# boardBase3.net
KiCad netlist of a schematic drawn in EAGLE
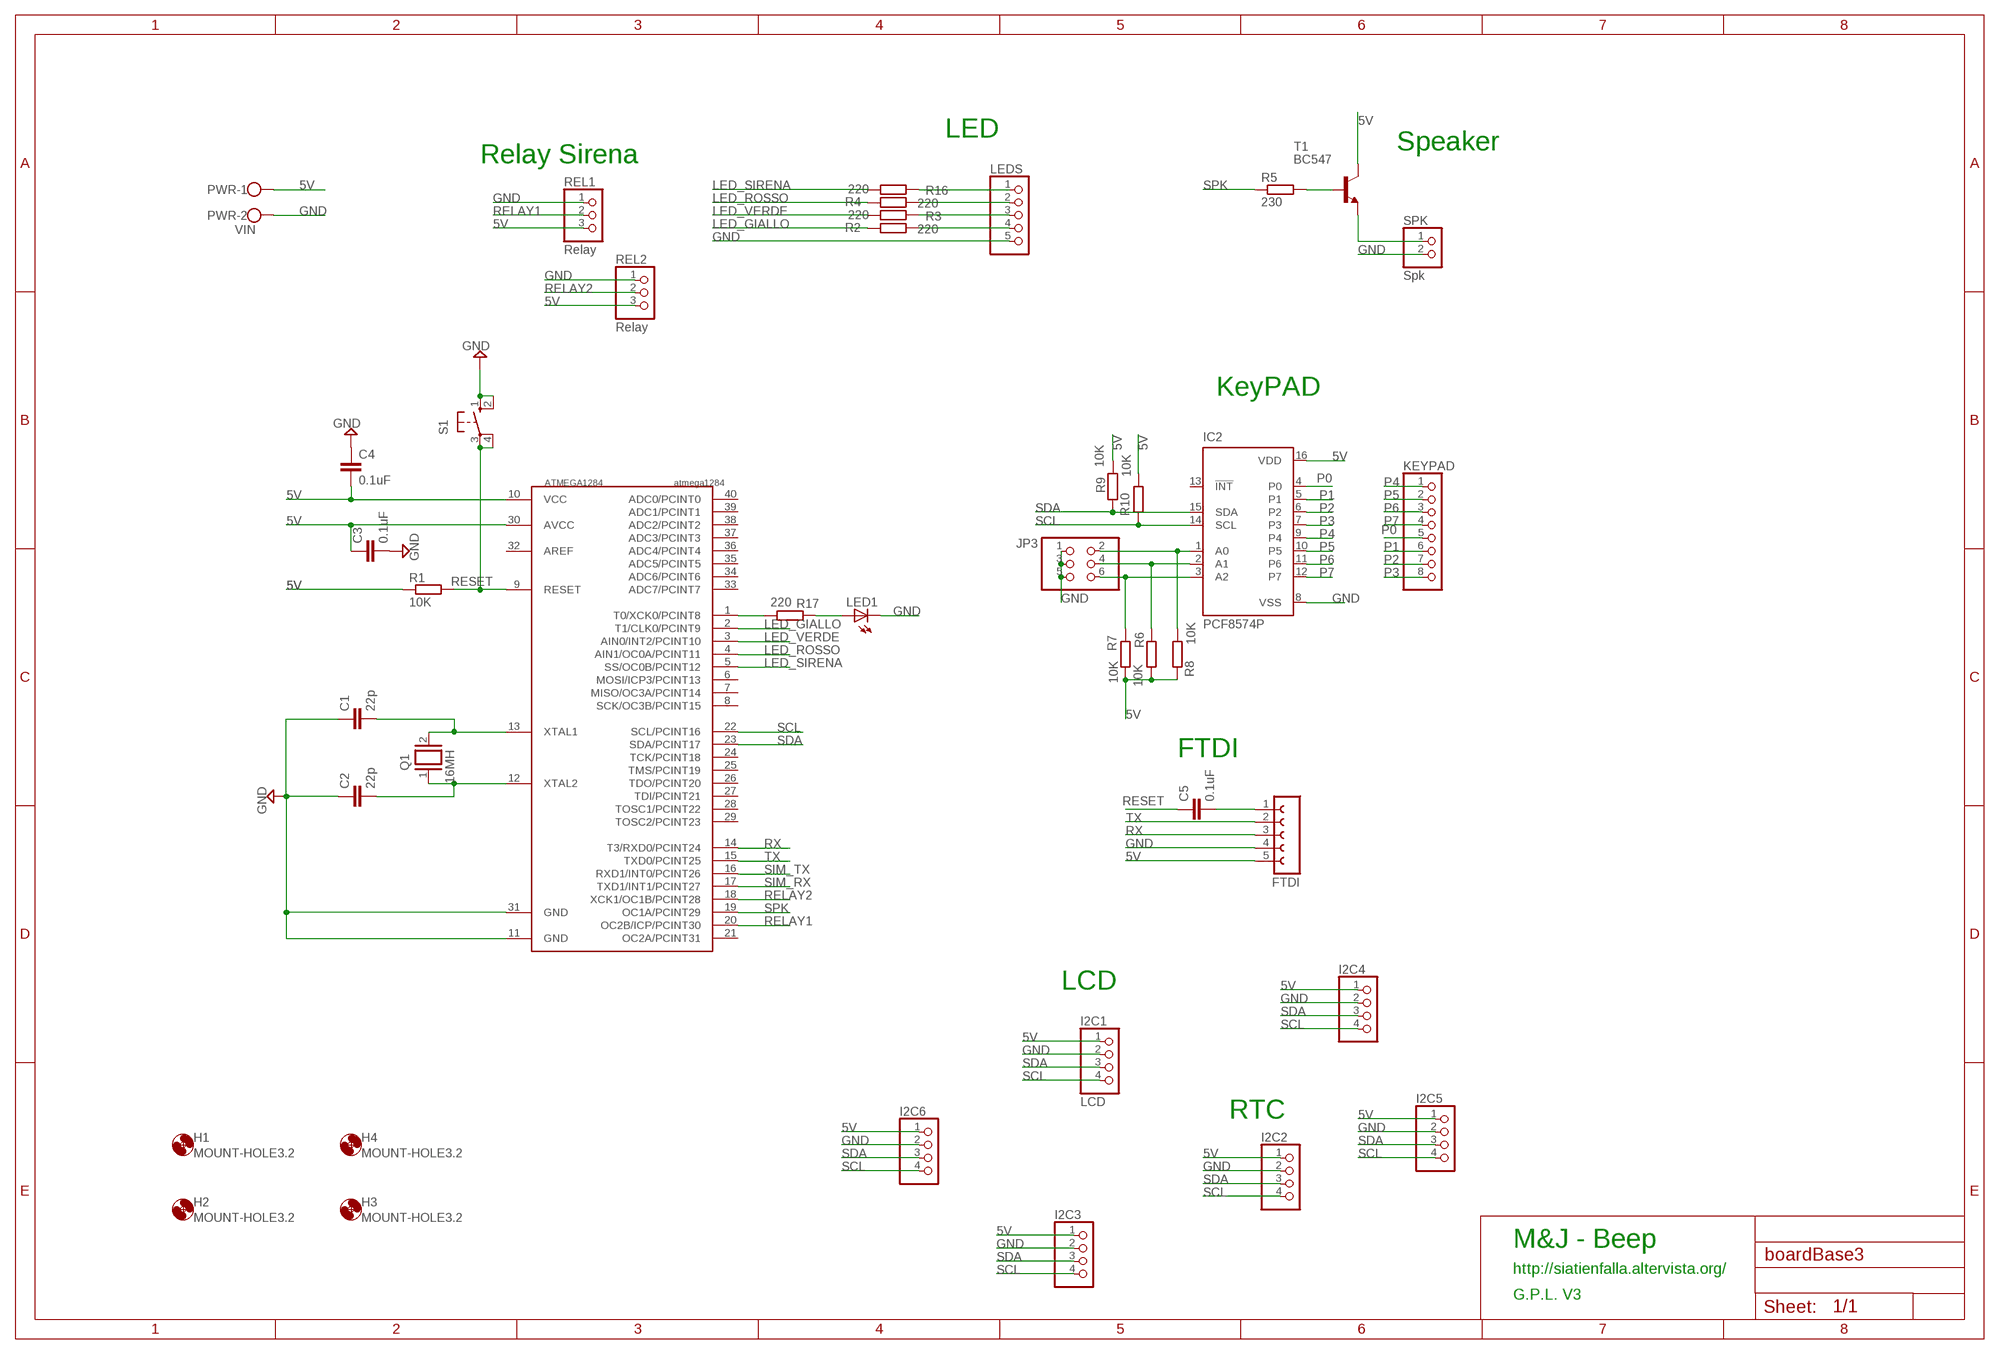
[diagram p0: schematic, sheet 1]

(export (version "E")
  (design (tool "Eeschema 10.0.6"))
  (components
    (comp (ref "ATMEGA1284")
      (value "atmega1284")
      (footprint "eagle-import:DIL40")
      (libsource (lib "eagle-import") (part "MEGA1284P"))
    )
    (comp (ref "C1")
      (value "22p")
      (footprint "eagle-import:C025-024X044")
      (libsource (lib "eagle-import") (part "C-EU025-024X044"))
    )
    (comp (ref "C2")
      (value "22p")
      (footprint "eagle-import:C025-024X044")
      (libsource (lib "eagle-import") (part "C-EU025-024X044"))
    )
    (comp (ref "C3")
      (value "0.1uF")
      (footprint "eagle-import:C025-025X050")
      (libsource (lib "eagle-import") (part "C-EU025-025X050"))
    )
    (comp (ref "C4")
      (value "0.1uF")
      (footprint "eagle-import:C025-025X050")
      (libsource (lib "eagle-import") (part "C-EU025-025X050"))
    )
    (comp (ref "C5")
      (value "0.1uF")
      (footprint "eagle-import:C025-025X050")
      (libsource (lib "eagle-import") (part "C-EU025-025X050"))
    )
    (comp (ref "FTDI")
      (value "FE05-1")
      (footprint "eagle-import:FE05-1")
      (libsource (lib "eagle-import") (part "FE05-1"))
    )
    (comp (ref "H1")
      (value "MOUNT-HOLE3.2")
      (footprint "eagle-import:3,2")
      (libsource (lib "eagle-import") (part "MOUNT-HOLE3.2"))
    )
    (comp (ref "H2")
      (value "MOUNT-HOLE3.2")
      (footprint "eagle-import:3,2")
      (libsource (lib "eagle-import") (part "MOUNT-HOLE3.2"))
    )
    (comp (ref "H3")
      (value "MOUNT-HOLE3.2")
      (footprint "eagle-import:3,2")
      (libsource (lib "eagle-import") (part "MOUNT-HOLE3.2"))
    )
    (comp (ref "H4")
      (value "MOUNT-HOLE3.2")
      (footprint "eagle-import:3,2")
      (libsource (lib "eagle-import") (part "MOUNT-HOLE3.2"))
    )
    (comp (ref "I2C1")
      (value "LCD")
      (footprint "eagle-import:1X04")
      (libsource (lib "eagle-import") (part "PINHD-1X4"))
    )
    (comp (ref "I2C2")
      (value "PINHD-1X4")
      (footprint "eagle-import:1X04")
      (libsource (lib "eagle-import") (part "PINHD-1X4"))
    )
    (comp (ref "I2C3")
      (value "PINHD-1X4")
      (footprint "eagle-import:1X04")
      (libsource (lib "eagle-import") (part "PINHD-1X4"))
    )
    (comp (ref "I2C4")
      (value "PINHD-1X4")
      (footprint "eagle-import:1X04")
      (libsource (lib "eagle-import") (part "PINHD-1X4"))
    )
    (comp (ref "I2C5")
      (value "PINHD-1X4")
      (footprint "eagle-import:1X04")
      (libsource (lib "eagle-import") (part "PINHD-1X4"))
    )
    (comp (ref "I2C6")
      (value "PINHD-1X4")
      (footprint "eagle-import:1X04")
      (libsource (lib "eagle-import") (part "PINHD-1X4"))
    )
    (comp (ref "IC2")
      (value "PCF8574P")
      (footprint "eagle-import:DIL16")
      (fields (field (name "MPN") "PCF8574PN"))
      (libsource (lib "eagle-import") (part "PCF8574P"))
    )
    (comp (ref "JP3")
      (value "PINHD-2X3")
      (footprint "eagle-import:2X03")
      (libsource (lib "eagle-import") (part "PINHD-2X3"))
    )
    (comp (ref "KEYPAD")
      (value "PINHD-1X8")
      (footprint "eagle-import:1X08")
      (libsource (lib "eagle-import") (part "PINHD-1X8"))
    )
    (comp (ref "LED1")
      (value "LED3MM")
      (footprint "eagle-import:LED3MM")
      (libsource (lib "eagle-import") (part "LED3MM"))
    )
    (comp (ref "LEDS")
      (value "PINHD-1X5")
      (footprint "eagle-import:1X05")
      (libsource (lib "eagle-import") (part "PINHD-1X5"))
    )
    (comp (ref "PWR")
      (value "VIN")
      (footprint "eagle-import:W237-102")
      (fields (field (name "MPN") "237-102"))
      (libsource (lib "eagle-import") (part "W237-102"))
    )
    (comp (ref "Q1")
      (value "16MH")
      (footprint "eagle-import:QS")
      (libsource (lib "eagle-import") (part "XTAL/S"))
    )
    (comp (ref "R1")
      (value "10K")
      (footprint "eagle-import:0207_10")
      (libsource (lib "eagle-import") (part "R-EU_0207/10"))
    )
    (comp (ref "R2")
      (value "220")
      (footprint "eagle-import:0207_2V")
      (libsource (lib "eagle-import") (part "R-EU_0207/2V"))
    )
    (comp (ref "R3")
      (value "220")
      (footprint "eagle-import:0207_2V")
      (libsource (lib "eagle-import") (part "R-EU_0207/2V"))
    )
    (comp (ref "R4")
      (value "220")
      (footprint "eagle-import:0207_2V")
      (libsource (lib "eagle-import") (part "R-EU_0207/2V"))
    )
    (comp (ref "R5")
      (value "230")
      (footprint "eagle-import:0207_2V")
      (libsource (lib "eagle-import") (part "R-EU_0207/2V"))
    )
    (comp (ref "R6")
      (value "10K")
      (footprint "eagle-import:0207_2V")
      (libsource (lib "eagle-import") (part "R-EU_0207/2V"))
    )
    (comp (ref "R7")
      (value "10K")
      (footprint "eagle-import:0207_2V")
      (libsource (lib "eagle-import") (part "R-EU_0207/2V"))
    )
    (comp (ref "R8")
      (value "10K")
      (footprint "eagle-import:0207_2V")
      (libsource (lib "eagle-import") (part "R-EU_0207/2V"))
    )
    (comp (ref "R9")
      (value "10K")
      (footprint "eagle-import:0207_2V")
      (libsource (lib "eagle-import") (part "R-EU_0207/2V"))
    )
    (comp (ref "R10")
      (value "10K")
      (footprint "eagle-import:0207_2V")
      (libsource (lib "eagle-import") (part "R-EU_0207/2V"))
    )
    (comp (ref "R16")
      (value "220")
      (footprint "eagle-import:0207_2V")
      (libsource (lib "eagle-import") (part "R-EU_0207/2V"))
    )
    (comp (ref "R17")
      (value "220")
      (footprint "eagle-import:0207_2V")
      (libsource (lib "eagle-import") (part "R-EU_0207/2V"))
    )
    (comp (ref "REL1")
      (value "Relay")
      (footprint "eagle-import:1X03")
      (libsource (lib "eagle-import") (part "PINHD-1X3"))
    )
    (comp (ref "REL2")
      (value "Relay")
      (footprint "eagle-import:1X03")
      (libsource (lib "eagle-import") (part "PINHD-1X3"))
    )
    (comp (ref "S1")
      (value "10-XX")
      (footprint "eagle-import:B3F-10XX")
      (fields (field (name "MPN") "B3F-1000"))
      (libsource (lib "eagle-import") (part "10-XX"))
    )
    (comp (ref "SPK")
      (value "Spk")
      (footprint "eagle-import:1X02")
      (libsource (lib "eagle-import") (part "PINHD-1X2"))
    )
    (comp (ref "T1")
      (value "BC547")
      (footprint "eagle-import:TO92")
      (libsource (lib "eagle-import") (part "BC547"))
    )
  )
  (nets
    (net (code "1") (name "/5V") (class "Default")
      (node (ref "ATMEGA1284") (pin "10") (pinfunction "VCC_10") (pintype "bidirectional"))
      (node (ref "ATMEGA1284") (pin "30") (pinfunction "AVCC_30") (pintype "bidirectional"))
      (node (ref "C3") (pin "1") (pinfunction "1_1") (pintype "passive"))
      (node (ref "C4") (pin "2") (pinfunction "2_2") (pintype "passive"))
      (node (ref "FTDI") (pin "5") (pinfunction "5_5") (pintype "passive"))
      (node (ref "I2C1") (pin "1") (pinfunction "1_1") (pintype "passive"))
      (node (ref "I2C2") (pin "1") (pinfunction "1_1") (pintype "passive"))
      (node (ref "I2C3") (pin "1") (pinfunction "1_1") (pintype "passive"))
      (node (ref "I2C4") (pin "1") (pinfunction "1_1") (pintype "passive"))
      (node (ref "I2C5") (pin "1") (pinfunction "1_1") (pintype "passive"))
      (node (ref "I2C6") (pin "1") (pinfunction "1_1") (pintype "passive"))
      (node (ref "IC2") (pin "16") (pinfunction "VDD_16") (pintype "power_in"))
      (node (ref "PWR") (pin "1") (pinfunction "KL_1") (pintype "passive"))
      (node (ref "R1") (pin "1") (pinfunction "1_1") (pintype "passive"))
      (node (ref "R10") (pin "1") (pinfunction "1_1") (pintype "passive"))
      (node (ref "R6") (pin "1") (pinfunction "1_1") (pintype "passive"))
      (node (ref "R7") (pin "2") (pinfunction "2_2") (pintype "passive"))
      (node (ref "R8") (pin "2") (pinfunction "2_2") (pintype "passive"))
      (node (ref "R9") (pin "2") (pinfunction "2_2") (pintype "passive"))
      (node (ref "REL1") (pin "3") (pinfunction "3_3") (pintype "passive"))
      (node (ref "REL2") (pin "3") (pinfunction "3_3") (pintype "passive"))
      (node (ref "T1") (pin "3") (pinfunction "C_3") (pintype "passive"))
    )
    (net (code "2") (name "/LED_GIALLO") (class "Default")
      (node (ref "ATMEGA1284") (pin "2") (pinfunction "T1/CLK0/PCINT9_2") (pintype "bidirectional"))
      (node (ref "R2") (pin "2") (pinfunction "2_2") (pintype "passive"))
    )
    (net (code "3") (name "/LED_ROSSO") (class "Default")
      (node (ref "ATMEGA1284") (pin "4") (pinfunction "AIN1/OC0A/PCINT11_4") (pintype "bidirectional"))
      (node (ref "R4") (pin "2") (pinfunction "2_2") (pintype "passive"))
    )
    (net (code "4") (name "/LED_SIRENA") (class "Default")
      (node (ref "ATMEGA1284") (pin "5") (pinfunction "SS/OC0B/PCINT12_5") (pintype "bidirectional"))
      (node (ref "R16") (pin "1") (pinfunction "1_1") (pintype "passive"))
    )
    (net (code "5") (name "/LED_VERDE") (class "Default")
      (node (ref "ATMEGA1284") (pin "3") (pinfunction "AIN0/INT2/PCINT10_3") (pintype "bidirectional"))
      (node (ref "R3") (pin "1") (pinfunction "1_1") (pintype "passive"))
    )
    (net (code "6") (name "/P0") (class "Default")
      (node (ref "IC2") (pin "4") (pinfunction "P0_4") (pintype "bidirectional"))
      (node (ref "KEYPAD") (pin "5") (pinfunction "5_5") (pintype "passive"))
    )
    (net (code "7") (name "/P1") (class "Default")
      (node (ref "IC2") (pin "5") (pinfunction "P1_5") (pintype "bidirectional"))
      (node (ref "KEYPAD") (pin "6") (pinfunction "6_6") (pintype "passive"))
    )
    (net (code "8") (name "/P2") (class "Default")
      (node (ref "IC2") (pin "6") (pinfunction "P2_6") (pintype "bidirectional"))
      (node (ref "KEYPAD") (pin "7") (pinfunction "7_7") (pintype "passive"))
    )
    (net (code "9") (name "/P3") (class "Default")
      (node (ref "IC2") (pin "7") (pinfunction "P3_7") (pintype "bidirectional"))
      (node (ref "KEYPAD") (pin "8") (pinfunction "8_8") (pintype "passive"))
    )
    (net (code "10") (name "/P4") (class "Default")
      (node (ref "IC2") (pin "9") (pinfunction "P4_9") (pintype "bidirectional"))
      (node (ref "KEYPAD") (pin "1") (pinfunction "1_1") (pintype "passive"))
    )
    (net (code "11") (name "/P5") (class "Default")
      (node (ref "IC2") (pin "10") (pinfunction "P5_10") (pintype "bidirectional"))
      (node (ref "KEYPAD") (pin "2") (pinfunction "2_2") (pintype "passive"))
    )
    (net (code "12") (name "/P6") (class "Default")
      (node (ref "IC2") (pin "11") (pinfunction "P6_11") (pintype "bidirectional"))
      (node (ref "KEYPAD") (pin "3") (pinfunction "3_3") (pintype "passive"))
    )
    (net (code "13") (name "/P7") (class "Default")
      (node (ref "IC2") (pin "12") (pinfunction "P7_12") (pintype "bidirectional"))
      (node (ref "KEYPAD") (pin "4") (pinfunction "4_4") (pintype "passive"))
    )
    (net (code "14") (name "/RELAY1") (class "Default")
      (node (ref "ATMEGA1284") (pin "20") (pinfunction "OC2B/ICP/PCINT30_20") (pintype "bidirectional"))
      (node (ref "REL1") (pin "2") (pinfunction "2_2") (pintype "passive"))
    )
    (net (code "15") (name "/RELAY2") (class "Default")
      (node (ref "ATMEGA1284") (pin "18") (pinfunction "XCK1/OC1B/PCINT28_18") (pintype "bidirectional"))
      (node (ref "REL2") (pin "2") (pinfunction "2_2") (pintype "passive"))
    )
    (net (code "16") (name "/RESET") (class "Default")
      (node (ref "ATMEGA1284") (pin "9") (pinfunction "RESET_9") (pintype "bidirectional"))
      (node (ref "C5") (pin "1") (pinfunction "1_1") (pintype "passive"))
      (node (ref "R1") (pin "2") (pinfunction "2_2") (pintype "passive"))
      (node (ref "S1") (pin "3") (pinfunction "P_3") (pintype "passive"))
      (node (ref "S1") (pin "4") (pinfunction "P1_4") (pintype "passive"))
    )
    (net (code "17") (name "/RX") (class "Default")
      (node (ref "ATMEGA1284") (pin "14") (pinfunction "T3/RXD0/PCINT24_14") (pintype "bidirectional"))
      (node (ref "FTDI") (pin "3") (pinfunction "3_3") (pintype "passive"))
    )
    (net (code "18") (name "/SCL") (class "Default")
      (node (ref "ATMEGA1284") (pin "22") (pinfunction "SCL/PCINT16_22") (pintype "bidirectional"))
      (node (ref "I2C1") (pin "4") (pinfunction "4_4") (pintype "passive"))
      (node (ref "I2C2") (pin "4") (pinfunction "4_4") (pintype "passive"))
      (node (ref "I2C3") (pin "4") (pinfunction "4_4") (pintype "passive"))
      (node (ref "I2C4") (pin "4") (pinfunction "4_4") (pintype "passive"))
      (node (ref "I2C5") (pin "4") (pinfunction "4_4") (pintype "passive"))
      (node (ref "I2C6") (pin "4") (pinfunction "4_4") (pintype "passive"))
      (node (ref "IC2") (pin "14") (pinfunction "SCL_14") (pintype "input"))
      (node (ref "R10") (pin "2") (pinfunction "2_2") (pintype "passive"))
    )
    (net (code "19") (name "/SDA") (class "Default")
      (node (ref "ATMEGA1284") (pin "23") (pinfunction "SDA/PCINT17_23") (pintype "bidirectional"))
      (node (ref "I2C1") (pin "3") (pinfunction "3_3") (pintype "passive"))
      (node (ref "I2C2") (pin "3") (pinfunction "3_3") (pintype "passive"))
      (node (ref "I2C3") (pin "3") (pinfunction "3_3") (pintype "passive"))
      (node (ref "I2C4") (pin "3") (pinfunction "3_3") (pintype "passive"))
      (node (ref "I2C5") (pin "3") (pinfunction "3_3") (pintype "passive"))
      (node (ref "I2C6") (pin "3") (pinfunction "3_3") (pintype "passive"))
      (node (ref "IC2") (pin "15") (pinfunction "SDA_15") (pintype "bidirectional"))
      (node (ref "R9") (pin "1") (pinfunction "1_1") (pintype "passive"))
    )
    (net (code "20") (name "/SIM_RX") (class "Default")
      (node (ref "ATMEGA1284") (pin "17") (pinfunction "TXD1/INT1/PCINT27_17") (pintype "bidirectional"))
    )
    (net (code "21") (name "/SIM_TX") (class "Default")
      (node (ref "ATMEGA1284") (pin "16") (pinfunction "RXD1/INT0/PCINT26_16") (pintype "bidirectional"))
    )
    (net (code "22") (name "/SPK") (class "Default")
      (node (ref "ATMEGA1284") (pin "19") (pinfunction "OC1A/PCINT29_19") (pintype "bidirectional"))
      (node (ref "R5") (pin "1") (pinfunction "1_1") (pintype "passive"))
    )
    (net (code "23") (name "/TX") (class "Default")
      (node (ref "ATMEGA1284") (pin "15") (pinfunction "TXD0/PCINT25_15") (pintype "bidirectional"))
      (node (ref "FTDI") (pin "2") (pinfunction "2_2") (pintype "passive"))
    )
    (net (code "24") (name "GND") (class "Default")
      (node (ref "ATMEGA1284") (pin "11") (pinfunction "GND_11") (pintype "bidirectional"))
      (node (ref "ATMEGA1284") (pin "31") (pinfunction "GND_31") (pintype "bidirectional"))
      (node (ref "C1") (pin "1") (pinfunction "1_1") (pintype "passive"))
      (node (ref "C2") (pin "1") (pinfunction "1_1") (pintype "passive"))
      (node (ref "C3") (pin "2") (pinfunction "2_2") (pintype "passive"))
      (node (ref "C4") (pin "1") (pinfunction "1_1") (pintype "passive"))
      (node (ref "FTDI") (pin "4") (pinfunction "4_4") (pintype "passive"))
      (node (ref "I2C1") (pin "2") (pinfunction "2_2") (pintype "passive"))
      (node (ref "I2C2") (pin "2") (pinfunction "2_2") (pintype "passive"))
      (node (ref "I2C3") (pin "2") (pinfunction "2_2") (pintype "passive"))
      (node (ref "I2C4") (pin "2") (pinfunction "2_2") (pintype "passive"))
      (node (ref "I2C5") (pin "2") (pinfunction "2_2") (pintype "passive"))
      (node (ref "I2C6") (pin "2") (pinfunction "2_2") (pintype "passive"))
      (node (ref "IC2") (pin "8") (pinfunction "VSS_8") (pintype "power_in"))
      (node (ref "JP3") (pin "1") (pinfunction "1_1") (pintype "passive"))
      (node (ref "JP3") (pin "3") (pinfunction "3_3") (pintype "passive"))
      (node (ref "JP3") (pin "5") (pinfunction "5_5") (pintype "passive"))
      (node (ref "LED1") (pin "K") (pinfunction "C_K") (pintype "passive"))
      (node (ref "LEDS") (pin "5") (pinfunction "5_5") (pintype "passive"))
      (node (ref "PWR") (pin "2") (pinfunction "KL_2") (pintype "passive"))
      (node (ref "REL1") (pin "1") (pinfunction "1_1") (pintype "passive"))
      (node (ref "REL2") (pin "1") (pinfunction "1_1") (pintype "passive"))
      (node (ref "S1") (pin "1") (pinfunction "S_1") (pintype "passive"))
      (node (ref "S1") (pin "2") (pinfunction "S1_2") (pintype "passive"))
      (node (ref "SPK") (pin "2") (pinfunction "2_2") (pintype "passive"))
    )
    (net (code "25") (name "Net-(ATMEGA1284-T0{slash}XCK0{slash}PCINT8)") (class "Default")
      (node (ref "ATMEGA1284") (pin "1") (pinfunction "T0/XCK0/PCINT8_1") (pintype "bidirectional"))
      (node (ref "R17") (pin "1") (pinfunction "1_1") (pintype "passive"))
    )
    (net (code "26") (name "Net-(ATMEGA1284-XTAL1)") (class "Default")
      (node (ref "ATMEGA1284") (pin "13") (pinfunction "XTAL1_13") (pintype "bidirectional"))
      (node (ref "C1") (pin "2") (pinfunction "2_2") (pintype "passive"))
      (node (ref "Q1") (pin "2") (pinfunction "2_2") (pintype "passive"))
    )
    (net (code "27") (name "Net-(ATMEGA1284-XTAL2)") (class "Default")
      (node (ref "ATMEGA1284") (pin "12") (pinfunction "XTAL2_12") (pintype "bidirectional"))
      (node (ref "C2") (pin "2") (pinfunction "2_2") (pintype "passive"))
      (node (ref "Q1") (pin "1") (pinfunction "1_1") (pintype "passive"))
    )
    (net (code "28") (name "Net-(C5-Pad2)") (class "Default")
      (node (ref "C5") (pin "2") (pinfunction "2_2") (pintype "passive"))
      (node (ref "FTDI") (pin "1") (pinfunction "1_1") (pintype "passive"))
    )
    (net (code "29") (name "Net-(IC2-A0)") (class "Default")
      (node (ref "IC2") (pin "1") (pinfunction "A0_1") (pintype "input"))
      (node (ref "JP3") (pin "2") (pinfunction "2_2") (pintype "passive"))
      (node (ref "R8") (pin "1") (pinfunction "1_1") (pintype "passive"))
    )
    (net (code "30") (name "Net-(IC2-A1)") (class "Default")
      (node (ref "IC2") (pin "2") (pinfunction "A1_2") (pintype "input"))
      (node (ref "JP3") (pin "4") (pinfunction "4_4") (pintype "passive"))
      (node (ref "R6") (pin "2") (pinfunction "2_2") (pintype "passive"))
    )
    (net (code "31") (name "Net-(IC2-A2)") (class "Default")
      (node (ref "IC2") (pin "3") (pinfunction "A2_3") (pintype "input"))
      (node (ref "JP3") (pin "6") (pinfunction "6_6") (pintype "passive"))
      (node (ref "R7") (pin "1") (pinfunction "1_1") (pintype "passive"))
    )
    (net (code "32") (name "Net-(LED1-PadA)") (class "Default")
      (node (ref "LED1") (pin "A") (pinfunction "A_A") (pintype "passive"))
      (node (ref "R17") (pin "2") (pinfunction "2_2") (pintype "passive"))
    )
    (net (code "33") (name "Net-(LEDS-Pad1)") (class "Default")
      (node (ref "LEDS") (pin "1") (pinfunction "1_1") (pintype "passive"))
      (node (ref "R16") (pin "2") (pinfunction "2_2") (pintype "passive"))
    )
    (net (code "34") (name "Net-(LEDS-Pad2)") (class "Default")
      (node (ref "LEDS") (pin "2") (pinfunction "2_2") (pintype "passive"))
      (node (ref "R4") (pin "1") (pinfunction "1_1") (pintype "passive"))
    )
    (net (code "35") (name "Net-(LEDS-Pad3)") (class "Default")
      (node (ref "LEDS") (pin "3") (pinfunction "3_3") (pintype "passive"))
      (node (ref "R3") (pin "2") (pinfunction "2_2") (pintype "passive"))
    )
    (net (code "36") (name "Net-(LEDS-Pad4)") (class "Default")
      (node (ref "LEDS") (pin "4") (pinfunction "4_4") (pintype "passive"))
      (node (ref "R2") (pin "1") (pinfunction "1_1") (pintype "passive"))
    )
    (net (code "37") (name "Net-(T1-B)") (class "Default")
      (node (ref "R5") (pin "2") (pinfunction "2_2") (pintype "passive"))
      (node (ref "T1") (pin "2") (pinfunction "B_2") (pintype "passive"))
    )
    (net (code "38") (name "Net-(T1-E)") (class "Default")
      (node (ref "SPK") (pin "1") (pinfunction "1_1") (pintype "passive"))
      (node (ref "T1") (pin "1") (pinfunction "E_1") (pintype "passive"))
    )
    (net (code "39") (name "unconnected-(ATMEGA1284-ADC0{slash}PCINT0-Pad40)") (class "Default")
      (node (ref "ATMEGA1284") (pin "40") (pinfunction "ADC0/PCINT0_40") (pintype "bidirectional"))
    )
    (net (code "40") (name "unconnected-(ATMEGA1284-ADC1{slash}PCINT1-Pad39)") (class "Default")
      (node (ref "ATMEGA1284") (pin "39") (pinfunction "ADC1/PCINT1_39") (pintype "bidirectional"))
    )
    (net (code "41") (name "unconnected-(ATMEGA1284-ADC2{slash}PCINT2-Pad38)") (class "Default")
      (node (ref "ATMEGA1284") (pin "38") (pinfunction "ADC2/PCINT2_38") (pintype "bidirectional"))
    )
    (net (code "42") (name "unconnected-(ATMEGA1284-ADC3{slash}PCINT3-Pad37)") (class "Default")
      (node (ref "ATMEGA1284") (pin "37") (pinfunction "ADC3/PCINT3_37") (pintype "bidirectional"))
    )
    (net (code "43") (name "unconnected-(ATMEGA1284-ADC4{slash}PCINT4-Pad36)") (class "Default")
      (node (ref "ATMEGA1284") (pin "36") (pinfunction "ADC4/PCINT4_36") (pintype "bidirectional"))
    )
    (net (code "44") (name "unconnected-(ATMEGA1284-ADC5{slash}PCINT5-Pad35)") (class "Default")
      (node (ref "ATMEGA1284") (pin "35") (pinfunction "ADC5/PCINT5_35") (pintype "bidirectional"))
    )
    (net (code "45") (name "unconnected-(ATMEGA1284-ADC6{slash}PCINT6-Pad34)") (class "Default")
      (node (ref "ATMEGA1284") (pin "34") (pinfunction "ADC6/PCINT6_34") (pintype "bidirectional"))
    )
    (net (code "46") (name "unconnected-(ATMEGA1284-ADC7{slash}PCINT7-Pad33)") (class "Default")
      (node (ref "ATMEGA1284") (pin "33") (pinfunction "ADC7/PCINT7_33") (pintype "bidirectional"))
    )
    (net (code "47") (name "unconnected-(ATMEGA1284-AREF-Pad32)") (class "Default")
      (node (ref "ATMEGA1284") (pin "32") (pinfunction "AREF_32") (pintype "bidirectional"))
    )
    (net (code "48") (name "unconnected-(ATMEGA1284-MISO{slash}OC3A{slash}PCINT14-Pad7)") (class "Default")
      (node (ref "ATMEGA1284") (pin "7") (pinfunction "MISO/OC3A/PCINT14_7") (pintype "bidirectional"))
    )
    (net (code "49") (name "unconnected-(ATMEGA1284-MOSI{slash}ICP3{slash}PCINT13-Pad6)") (class "Default")
      (node (ref "ATMEGA1284") (pin "6") (pinfunction "MOSI/ICP3/PCINT13_6") (pintype "bidirectional"))
    )
    (net (code "50") (name "unconnected-(ATMEGA1284-OC2A{slash}PCINT31-Pad21)") (class "Default")
      (node (ref "ATMEGA1284") (pin "21") (pinfunction "OC2A/PCINT31_21") (pintype "bidirectional"))
    )
    (net (code "51") (name "unconnected-(ATMEGA1284-SCK{slash}OC3B{slash}PCINT15-Pad8)") (class "Default")
      (node (ref "ATMEGA1284") (pin "8") (pinfunction "SCK/OC3B/PCINT15_8") (pintype "bidirectional"))
    )
    (net (code "52") (name "unconnected-(ATMEGA1284-TCK{slash}PCINT18-Pad24)") (class "Default")
      (node (ref "ATMEGA1284") (pin "24") (pinfunction "TCK/PCINT18_24") (pintype "bidirectional"))
    )
    (net (code "53") (name "unconnected-(ATMEGA1284-TDI{slash}PCINT21-Pad27)") (class "Default")
      (node (ref "ATMEGA1284") (pin "27") (pinfunction "TDI/PCINT21_27") (pintype "bidirectional"))
    )
    (net (code "54") (name "unconnected-(ATMEGA1284-TDO{slash}PCINT20-Pad26)") (class "Default")
      (node (ref "ATMEGA1284") (pin "26") (pinfunction "TDO/PCINT20_26") (pintype "bidirectional"))
    )
    (net (code "55") (name "unconnected-(ATMEGA1284-TMS{slash}PCINT19-Pad25)") (class "Default")
      (node (ref "ATMEGA1284") (pin "25") (pinfunction "TMS/PCINT19_25") (pintype "bidirectional"))
    )
    (net (code "56") (name "unconnected-(ATMEGA1284-TOSC1{slash}PCINT22-Pad28)") (class "Default")
      (node (ref "ATMEGA1284") (pin "28") (pinfunction "TOSC1/PCINT22_28") (pintype "bidirectional"))
    )
    (net (code "57") (name "unconnected-(ATMEGA1284-TOSC2{slash}PCINT23-Pad29)") (class "Default")
      (node (ref "ATMEGA1284") (pin "29") (pinfunction "TOSC2/PCINT23_29") (pintype "bidirectional"))
    )
    (net (code "58") (name "unconnected-(IC2-~{INT}-Pad13)") (class "Default")
      (node (ref "IC2") (pin "13") (pinfunction "~{INT}_13") (pintype "output"))
    )
  )
)
